# MCU_GATEWAY.net
KiCad netlist of a schematic drawn in Altium Designer
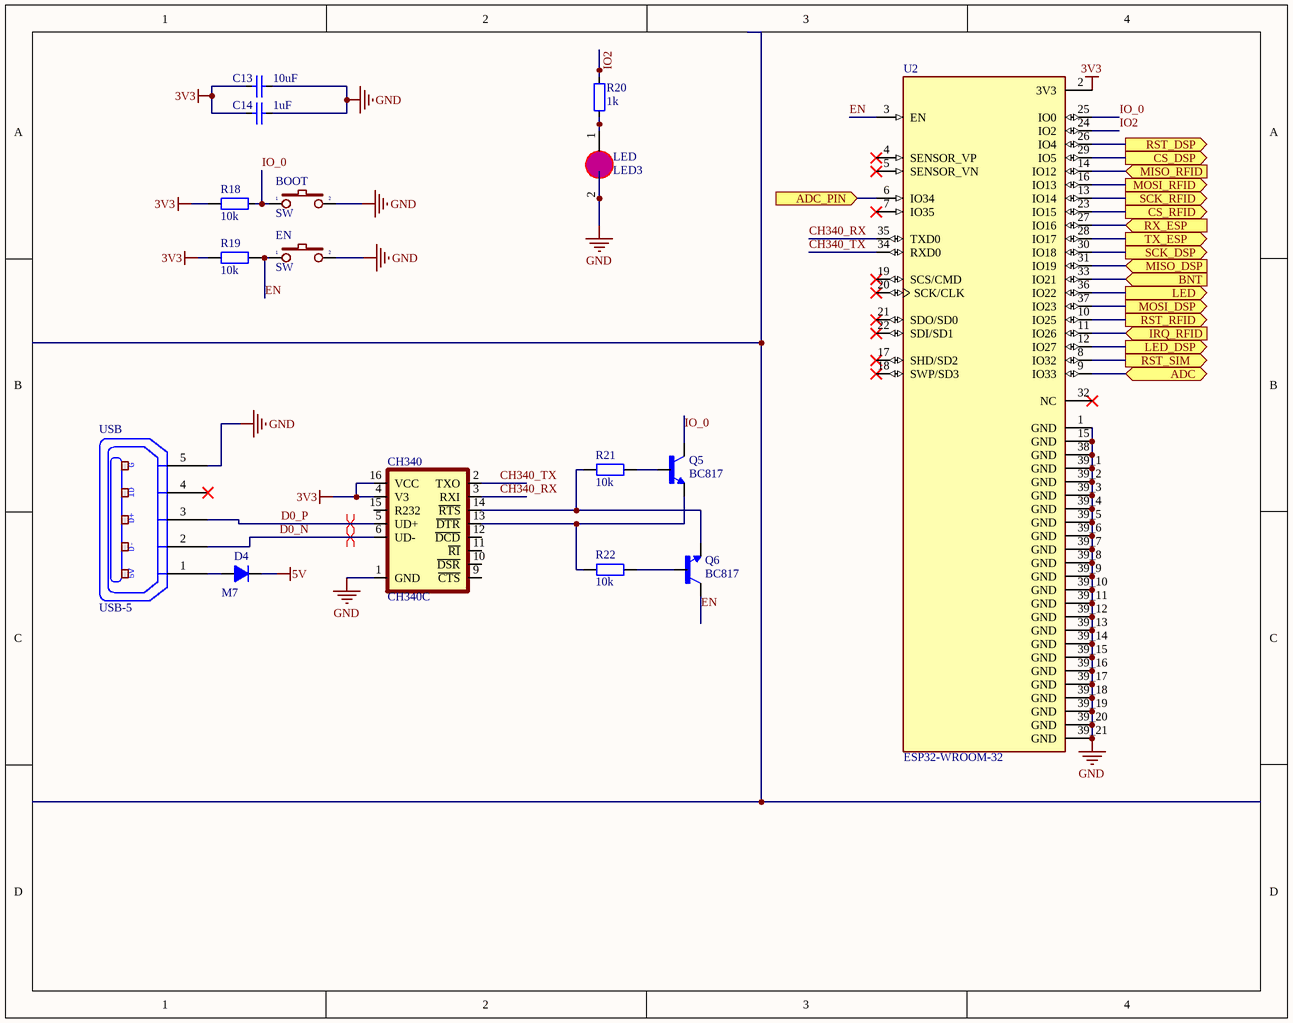
[diagram p0: MCU_GATEWAY.SchDoc]

(export (version "E")
  (design (tool "Eeschema 10.0.6"))
  (components
    (comp (ref "BOOT")
      (value "SW")
      (footprint "SW-SMD")
      (description "Switch button 2 pin")
      (libsource (lib "My Library") (part "SW2"))
    )
    (comp (ref "C13")
      (value "10uF")
      (footprint "CAP_0603")
      (description "Capacitor")
      (fields (field (name "PUBLISHER") "Altium Limited"))
      (libsource (lib "My Library") (part "CapSMD"))
    )
    (comp (ref "C14")
      (value "1uF")
      (footprint "CAP_0603")
      (description "Capacitor")
      (fields (field (name "PUBLISHER") "Altium Limited"))
      (libsource (lib "My Library") (part "CapSMD"))
    )
    (comp (ref "CH340")
      (value "CH340C")
      (footprint "SOP-16")
      (description "USB to serial chip CH340")
      (fields (field (name "MF") "WCH"))
      (libsource (lib "My Library") (part "CH340C"))
    )
    (comp (ref "D4")
      (value "M7")
      (footprint "SMA")
      (description "Diode 1A")
      (libsource (lib "Main") (part "D1A"))
    )
    (comp (ref "EN")
      (value "SW")
      (footprint "SW-SMD")
      (description "Switch button 2 pin")
      (libsource (lib "My Library") (part "SW2"))
    )
    (comp (ref "LED")
      (value "LED3")
      (footprint "LED0805")
      (description "LED SMD 0805")
      (libsource (lib "My Library 2") (part "LED0805"))
    )
    (comp (ref "Q5")
      (value "BC817")
      (footprint "SOT95P240X97-3N")
      (description "Bipolar (BJT) Transistor NPN 45V 500mA 100MHz 250mW Surface Mount TO-236AB")
      (fields (field (name "MF") "Rectron"))
      (libsource (lib "") (part "BC817_1"))
    )
    (comp (ref "Q6")
      (value "BC817")
      (footprint "SOT95P240X97-3N")
      (description "Bipolar (BJT) Transistor NPN 45V 500mA 100MHz 250mW Surface Mount TO-236AB")
      (fields (field (name "MF") "Rectron"))
      (libsource (lib "BC817") (part "BC817"))
    )
    (comp (ref "R18")
      (value "10k")
      (footprint "RES-SMD-0603")
      (description "Resistor SMD")
      (fields
        (field (name "MANUFACTURER") "Generic Components")
        (field (name "PUBLISHER") "Altium Hobart Technology Centre")
      )
      (libsource (lib "My Library") (part "Resistor - SMD"))
    )
    (comp (ref "R19")
      (value "10k")
      (footprint "RES-SMD-0603")
      (description "Resistor SMD")
      (fields
        (field (name "MANUFACTURER") "Generic Components")
        (field (name "PUBLISHER") "Altium Hobart Technology Centre")
      )
      (libsource (lib "My Library") (part "Resistor - SMD"))
    )
    (comp (ref "R20")
      (value "1k")
      (footprint "RES-SMD-0603")
      (description "Resistor SMD")
      (fields
        (field (name "MANUFACTURER") "Generic Components")
        (field (name "PUBLISHER") "Altium Hobart Technology Centre")
      )
      (libsource (lib "My Library") (part "Resistor - SMD"))
    )
    (comp (ref "R21")
      (value "10k")
      (footprint "RES-SMD-0603")
      (description "Resistor SMD")
      (fields
        (field (name "MANUFACTURER") "Generic Components")
        (field (name "PUBLISHER") "Altium Hobart Technology Centre")
      )
      (libsource (lib "My Library") (part "Resistor - SMD"))
    )
    (comp (ref "R22")
      (value "10k")
      (footprint "RES-SMD-0603")
      (description "Resistor SMD")
      (fields
        (field (name "MANUFACTURER") "Generic Components")
        (field (name "PUBLISHER") "Altium Hobart Technology Centre")
      )
      (libsource (lib "My Library") (part "Resistor - SMD"))
    )
    (comp (ref "U2")
      (value "ESP32-WROOM-32")
      (footprint "MODULE_ESP32-WROOM-32")
      (fields (field (name "MF") "Espressif Systems"))
      (libsource (lib "ESP32-WROOM-32") (part "ESP32-WROOM-32"))
    )
    (comp (ref "USB")
      (value "USB-5")
      (footprint "USB-M1")
      (fields
        (field (name "MANUFACTURER") "FCI")
        (field (name "MANUFACTURER PART NUMBER") "10118193-0001LF")
        (field (name ".CREATOR") "MM")
        (field (name ".CHECKED PCB") "RF")
        (field (name ".CHECKED SCH") "MM")
      )
      (libsource (lib "My Library 2") (part "USB-5"))
    )
  )
  (nets
    (net (code "1") (name "/ADC") (class "Default")
      (node (ref "U2") (pin "9") (pinfunction "IO33_9") (pintype "bidirectional"))
    )
    (net (code "2") (name "/ADC_PIN") (class "Default")
      (node (ref "U2") (pin "6") (pinfunction "IO34_6") (pintype "input"))
    )
    (net (code "3") (name "/BNT") (class "Default")
      (node (ref "U2") (pin "33") (pinfunction "IO21_33") (pintype "bidirectional"))
    )
    (net (code "4") (name "/CH340_RX") (class "Default")
      (node (ref "CH340") (pin "3") (pinfunction "RXI_3") (pintype "bidirectional"))
      (node (ref "U2") (pin "35") (pinfunction "TXD0_35") (pintype "bidirectional"))
    )
    (net (code "5") (name "/CH340_TX") (class "Default")
      (node (ref "CH340") (pin "2") (pinfunction "TXO_2") (pintype "bidirectional"))
      (node (ref "U2") (pin "34") (pinfunction "RXD0_34") (pintype "bidirectional"))
    )
    (net (code "6") (name "/CS_DSP") (class "Default")
      (node (ref "U2") (pin "29") (pinfunction "IO5_29") (pintype "bidirectional"))
    )
    (net (code "7") (name "/CS_RFID") (class "Default")
      (node (ref "U2") (pin "23") (pinfunction "IO15_23") (pintype "bidirectional"))
    )
    (net (code "8") (name "/D0_N") (class "Default")
      (node (ref "CH340") (pin "6") (pinfunction "UD-_6") (pintype "bidirectional"))
      (node (ref "USB") (pin "2") (pinfunction "P2_2") (pintype "passive"))
    )
    (net (code "9") (name "/D0_P") (class "Default")
      (node (ref "CH340") (pin "5") (pinfunction "UD+_5") (pintype "bidirectional"))
      (node (ref "USB") (pin "3") (pinfunction "P3_3") (pintype "passive"))
    )
    (net (code "10") (name "/EN") (class "Default")
      (node (ref "EN") (pin "1") (pinfunction "1_1") (pintype "passive"))
      (node (ref "Q6") (pin "3") (pinfunction "C_3") (pintype "passive"))
      (node (ref "R19") (pin "2") (pinfunction "2_2") (pintype "passive"))
      (node (ref "U2") (pin "3") (pinfunction "EN_3") (pintype "input"))
    )
    (net (code "11") (name "/IO2") (class "Default")
      (node (ref "R20") (pin "1") (pinfunction "1_1") (pintype "passive"))
      (node (ref "U2") (pin "24") (pinfunction "IO2_24") (pintype "bidirectional"))
    )
    (net (code "12") (name "/IO_0") (class "Default")
      (node (ref "BOOT") (pin "1") (pinfunction "1_1") (pintype "passive"))
      (node (ref "Q5") (pin "3") (pinfunction "C_3") (pintype "passive"))
      (node (ref "R18") (pin "2") (pinfunction "2_2") (pintype "passive"))
      (node (ref "U2") (pin "25") (pinfunction "IO0_25") (pintype "bidirectional"))
    )
    (net (code "13") (name "/IRQ_RFID") (class "Default")
      (node (ref "U2") (pin "11") (pinfunction "IO26_11") (pintype "bidirectional"))
    )
    (net (code "14") (name "/LED") (class "Default")
      (node (ref "U2") (pin "36") (pinfunction "IO22_36") (pintype "bidirectional"))
    )
    (net (code "15") (name "/LED_DSP") (class "Default")
      (node (ref "U2") (pin "12") (pinfunction "IO27_12") (pintype "bidirectional"))
    )
    (net (code "16") (name "/MISO_DSP") (class "Default")
      (node (ref "U2") (pin "31") (pinfunction "IO19_31") (pintype "bidirectional"))
    )
    (net (code "17") (name "/MISO_RFID") (class "Default")
      (node (ref "U2") (pin "14") (pinfunction "IO12_14") (pintype "bidirectional"))
    )
    (net (code "18") (name "/MOSI_DSP") (class "Default")
      (node (ref "U2") (pin "37") (pinfunction "IO23_37") (pintype "bidirectional"))
    )
    (net (code "19") (name "/MOSI_RFID") (class "Default")
      (node (ref "U2") (pin "16") (pinfunction "IO13_16") (pintype "bidirectional"))
    )
    (net (code "20") (name "/RST_DSP") (class "Default")
      (node (ref "U2") (pin "26") (pinfunction "IO4_26") (pintype "bidirectional"))
    )
    (net (code "21") (name "/RST_RFID") (class "Default")
      (node (ref "U2") (pin "10") (pinfunction "IO25_10") (pintype "bidirectional"))
    )
    (net (code "22") (name "/RST_SIM") (class "Default")
      (node (ref "U2") (pin "8") (pinfunction "IO32_8") (pintype "bidirectional"))
    )
    (net (code "23") (name "/RX_ESP") (class "Default")
      (node (ref "U2") (pin "27") (pinfunction "IO16_27") (pintype "bidirectional"))
    )
    (net (code "24") (name "/SCK_DSP") (class "Default")
      (node (ref "U2") (pin "30") (pinfunction "IO18_30") (pintype "bidirectional"))
    )
    (net (code "25") (name "/SCK_RFID") (class "Default")
      (node (ref "U2") (pin "13") (pinfunction "IO14_13") (pintype "bidirectional"))
    )
    (net (code "26") (name "/TX_ESP") (class "Default")
      (node (ref "U2") (pin "28") (pinfunction "IO17_28") (pintype "bidirectional"))
    )
    (net (code "27") (name "3V3") (class "Default")
      (node (ref "C13") (pin "1") (pinfunction "1_1") (pintype "passive"))
      (node (ref "C14") (pin "1") (pinfunction "1_1") (pintype "passive"))
      (node (ref "CH340") (pin "16") (pinfunction "VCC_16") (pintype "bidirectional"))
      (node (ref "CH340") (pin "4") (pinfunction "V3_4") (pintype "bidirectional"))
      (node (ref "R18") (pin "1") (pinfunction "1_1") (pintype "passive"))
      (node (ref "R19") (pin "1") (pinfunction "1_1") (pintype "passive"))
      (node (ref "U2") (pin "2") (pinfunction "3V3_2") (pintype "power_in"))
    )
    (net (code "28") (name "5V") (class "Default")
      (node (ref "D4") (pin "2") (pinfunction "K_2") (pintype "passive"))
    )
    (net (code "29") (name "GND") (class "Default")
      (node (ref "BOOT") (pin "2") (pinfunction "2_2") (pintype "passive"))
      (node (ref "C13") (pin "2") (pinfunction "2_2") (pintype "passive"))
      (node (ref "C14") (pin "2") (pinfunction "2_2") (pintype "passive"))
      (node (ref "CH340") (pin "1") (pinfunction "GND_1") (pintype "bidirectional"))
      (node (ref "EN") (pin "2") (pinfunction "2_2") (pintype "passive"))
      (node (ref "LED") (pin "2") (pinfunction "K_2") (pintype "passive"))
      (node (ref "U2") (pin "1") (pinfunction "GND_1") (pintype "power_in"))
      (node (ref "U2") (pin "15") (pinfunction "GND_15") (pintype "power_in"))
      (node (ref "U2") (pin "38") (pinfunction "GND_38") (pintype "power_in"))
      (node (ref "U2") (pin "39_1") (pinfunction "GND_39_1") (pintype "power_in"))
      (node (ref "U2") (pin "39_10") (pinfunction "GND_39_10") (pintype "power_in"))
      (node (ref "U2") (pin "39_11") (pinfunction "GND_39_11") (pintype "power_in"))
      (node (ref "U2") (pin "39_12") (pinfunction "GND_39_12") (pintype "power_in"))
      (node (ref "U2") (pin "39_13") (pinfunction "GND_39_13") (pintype "power_in"))
      (node (ref "U2") (pin "39_14") (pinfunction "GND_39_14") (pintype "power_in"))
      (node (ref "U2") (pin "39_15") (pinfunction "GND_39_15") (pintype "power_in"))
      (node (ref "U2") (pin "39_16") (pinfunction "GND_39_16") (pintype "power_in"))
      (node (ref "U2") (pin "39_17") (pinfunction "GND_39_17") (pintype "power_in"))
      (node (ref "U2") (pin "39_18") (pinfunction "GND_39_18") (pintype "power_in"))
      (node (ref "U2") (pin "39_19") (pinfunction "GND_39_19") (pintype "power_in"))
      (node (ref "U2") (pin "39_2") (pinfunction "GND_39_2") (pintype "power_in"))
      (node (ref "U2") (pin "39_20") (pinfunction "GND_39_20") (pintype "power_in"))
      (node (ref "U2") (pin "39_21") (pinfunction "GND_39_21") (pintype "power_in"))
      (node (ref "U2") (pin "39_3") (pinfunction "GND_39_3") (pintype "power_in"))
      (node (ref "U2") (pin "39_4") (pinfunction "GND_39_4") (pintype "power_in"))
      (node (ref "U2") (pin "39_5") (pinfunction "GND_39_5") (pintype "power_in"))
      (node (ref "U2") (pin "39_6") (pinfunction "GND_39_6") (pintype "power_in"))
      (node (ref "U2") (pin "39_7") (pinfunction "GND_39_7") (pintype "power_in"))
      (node (ref "U2") (pin "39_8") (pinfunction "GND_39_8") (pintype "power_in"))
      (node (ref "U2") (pin "39_9") (pinfunction "GND_39_9") (pintype "power_in"))
      (node (ref "USB") (pin "5") (pinfunction "P5_5") (pintype "passive"))
    )
    (net (code "30") (name "Net-(CH340-~{DTR})") (class "Default")
      (node (ref "CH340") (pin "13") (pinfunction "~{DTR}_13") (pintype "bidirectional"))
      (node (ref "Q5") (pin "2") (pinfunction "E_2") (pintype "passive"))
      (node (ref "R22") (pin "1") (pinfunction "1_1") (pintype "passive"))
    )
    (net (code "31") (name "Net-(CH340-~{RTS})") (class "Default")
      (node (ref "CH340") (pin "14") (pinfunction "~{RTS}_14") (pintype "bidirectional"))
      (node (ref "Q6") (pin "2") (pinfunction "E_2") (pintype "passive"))
      (node (ref "R21") (pin "1") (pinfunction "1_1") (pintype "passive"))
    )
    (net (code "32") (name "Net-(D4-A)") (class "Default")
      (node (ref "D4") (pin "1") (pinfunction "A_1") (pintype "passive"))
      (node (ref "USB") (pin "1") (pinfunction "P1_1") (pintype "passive"))
    )
    (net (code "33") (name "Net-(LED-A)") (class "Default")
      (node (ref "LED") (pin "1") (pinfunction "A_1") (pintype "passive"))
      (node (ref "R20") (pin "2") (pinfunction "2_2") (pintype "passive"))
    )
    (net (code "34") (name "Net-(Q5-B)") (class "Default")
      (node (ref "Q5") (pin "1") (pinfunction "B_1") (pintype "passive"))
      (node (ref "R21") (pin "2") (pinfunction "2_2") (pintype "passive"))
    )
    (net (code "35") (name "Net-(Q6-B)") (class "Default")
      (node (ref "Q6") (pin "1") (pinfunction "B_1") (pintype "passive"))
      (node (ref "R22") (pin "2") (pinfunction "2_2") (pintype "passive"))
    )
    (net (code "36") (name "unconnected-(CH340-R232-Pad15)") (class "Default")
      (node (ref "CH340") (pin "15") (pinfunction "R232_15") (pintype "bidirectional"))
    )
    (net (code "37") (name "unconnected-(CH340-~{CTS}-Pad9)") (class "Default")
      (node (ref "CH340") (pin "9") (pinfunction "~{CTS}_9") (pintype "bidirectional"))
    )
    (net (code "38") (name "unconnected-(CH340-~{DCD}-Pad12)") (class "Default")
      (node (ref "CH340") (pin "12") (pinfunction "~{DCD}_12") (pintype "bidirectional"))
    )
    (net (code "39") (name "unconnected-(CH340-~{DSR}-Pad10)") (class "Default")
      (node (ref "CH340") (pin "10") (pinfunction "~{DSR}_10") (pintype "bidirectional"))
    )
    (net (code "40") (name "unconnected-(CH340-~{RI}-Pad11)") (class "Default")
      (node (ref "CH340") (pin "11") (pinfunction "~{RI}_11") (pintype "bidirectional"))
    )
    (net (code "41") (name "unconnected-(U2-IO35-Pad7)") (class "Default")
      (node (ref "U2") (pin "7") (pinfunction "IO35_7") (pintype "input+no_connect"))
    )
    (net (code "42") (name "unconnected-(U2-NC-Pad32)") (class "Default")
      (node (ref "U2") (pin "32") (pinfunction "NC_32") (pintype "passive+no_connect"))
    )
    (net (code "43") (name "unconnected-(U2-SCK{slash}CLK-Pad20)") (class "Default")
      (node (ref "U2") (pin "20") (pinfunction "SCK/CLK_20") (pintype "bidirectional+no_connect"))
    )
    (net (code "44") (name "unconnected-(U2-SCS{slash}CMD-Pad19)") (class "Default")
      (node (ref "U2") (pin "19") (pinfunction "SCS/CMD_19") (pintype "bidirectional+no_connect"))
    )
    (net (code "45") (name "unconnected-(U2-SDI{slash}SD1-Pad22)") (class "Default")
      (node (ref "U2") (pin "22") (pinfunction "SDI/SD1_22") (pintype "bidirectional+no_connect"))
    )
    (net (code "46") (name "unconnected-(U2-SDO{slash}SD0-Pad21)") (class "Default")
      (node (ref "U2") (pin "21") (pinfunction "SDO/SD0_21") (pintype "bidirectional+no_connect"))
    )
    (net (code "47") (name "unconnected-(U2-SENSOR_VN-Pad5)") (class "Default")
      (node (ref "U2") (pin "5") (pinfunction "SENSOR_VN_5") (pintype "input+no_connect"))
    )
    (net (code "48") (name "unconnected-(U2-SENSOR_VP-Pad4)") (class "Default")
      (node (ref "U2") (pin "4") (pinfunction "SENSOR_VP_4") (pintype "input+no_connect"))
    )
    (net (code "49") (name "unconnected-(U2-SHD{slash}SD2-Pad17)") (class "Default")
      (node (ref "U2") (pin "17") (pinfunction "SHD/SD2_17") (pintype "bidirectional+no_connect"))
    )
    (net (code "50") (name "unconnected-(U2-SWP{slash}SD3-Pad18)") (class "Default")
      (node (ref "U2") (pin "18") (pinfunction "SWP/SD3_18") (pintype "bidirectional+no_connect"))
    )
    (net (code "51") (name "unconnected-(USB-P4-Pad4)") (class "Default")
      (node (ref "USB") (pin "4") (pinfunction "P4_4") (pintype "passive+no_connect"))
    )
  )
)
